# DAC_GainOutputStage8.net
KiCad netlist of a schematic drawn in EAGLE
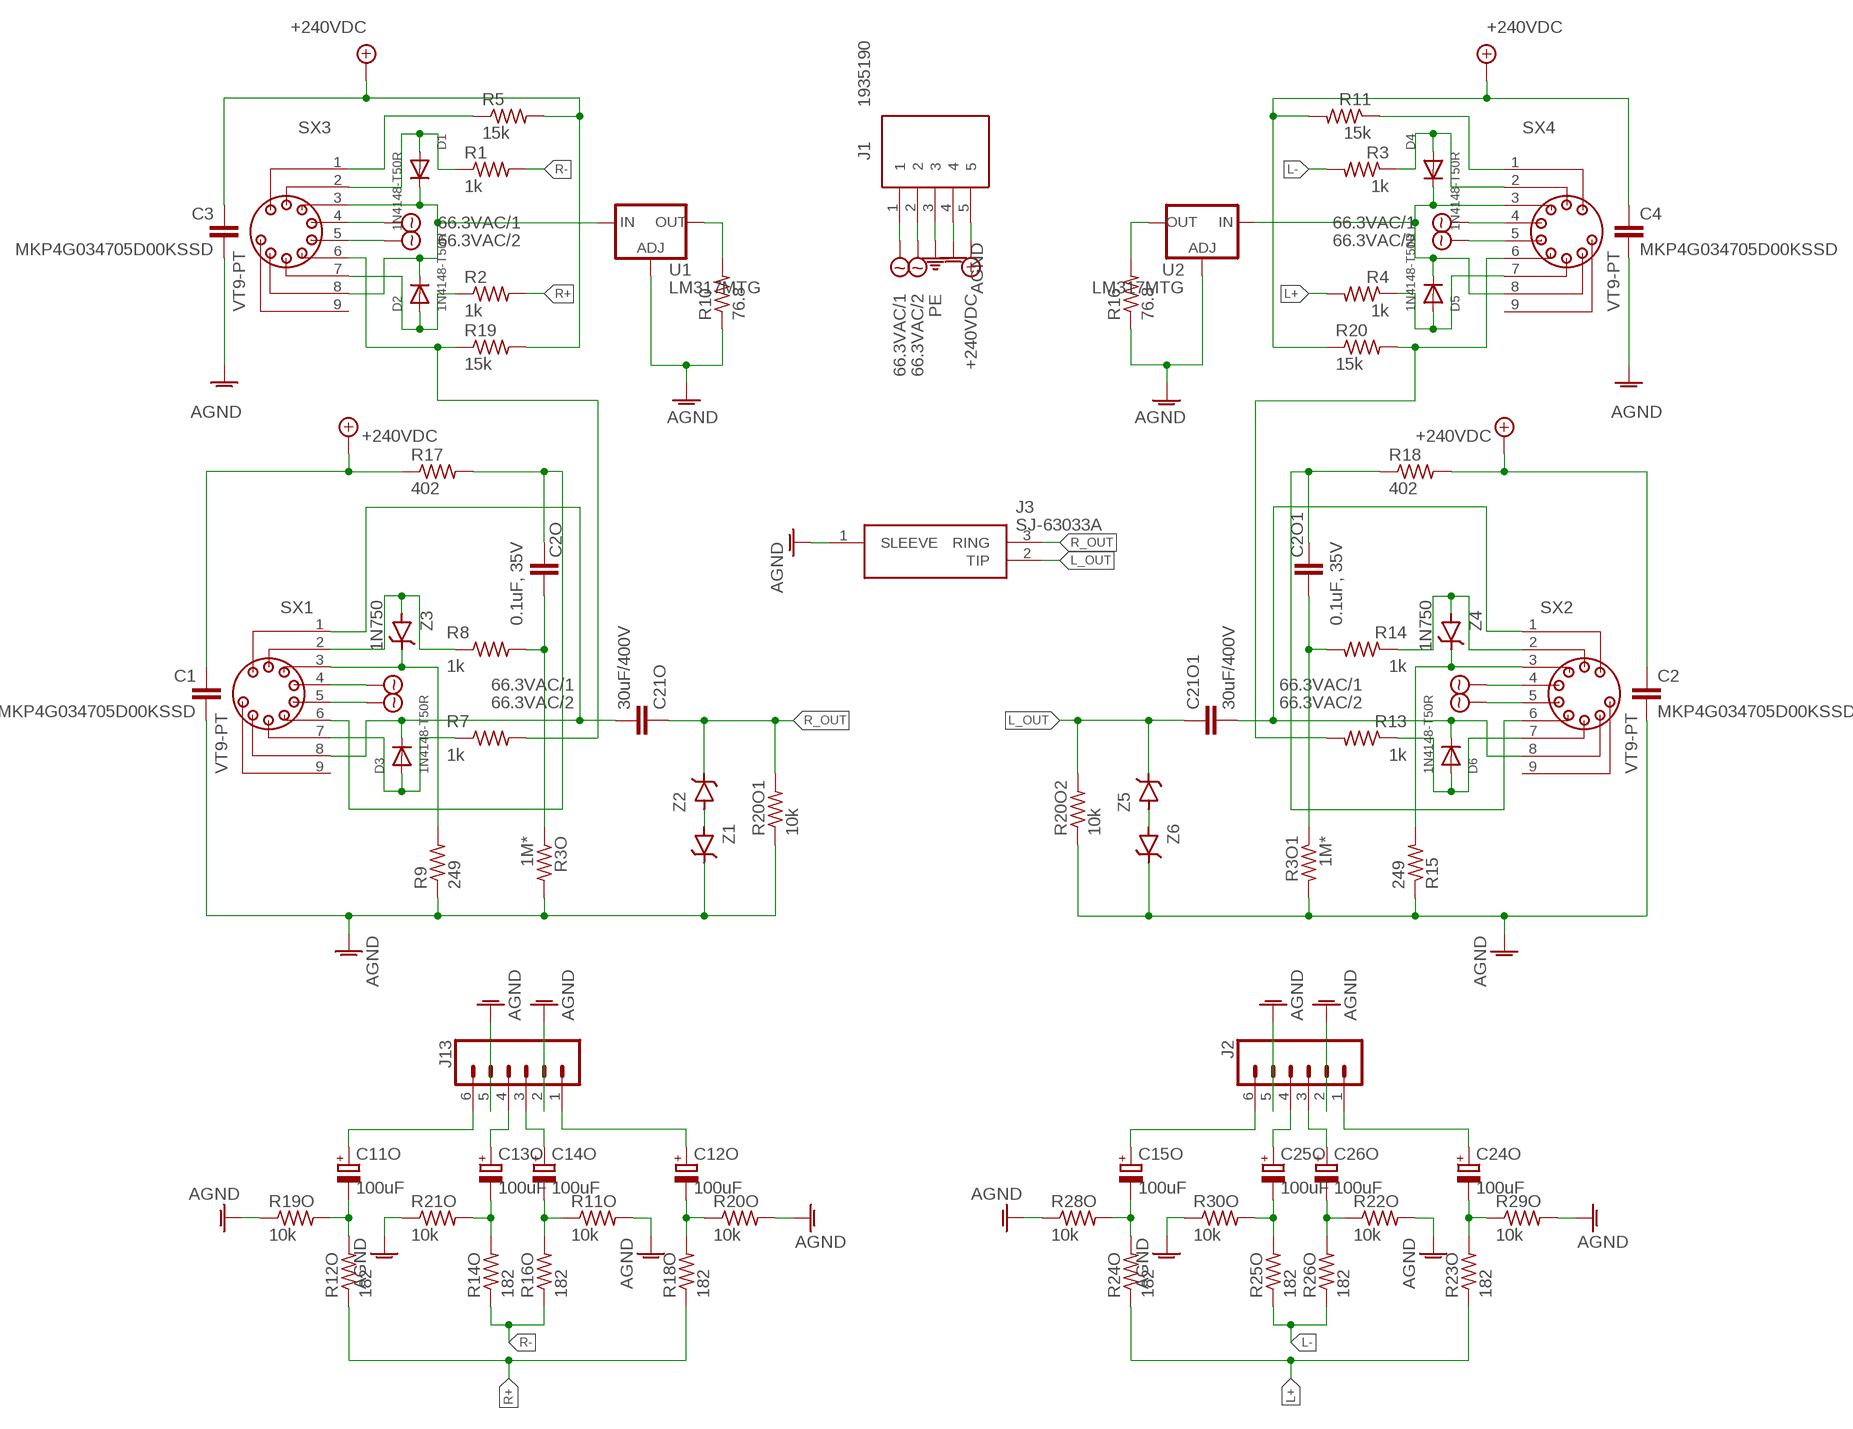
[diagram p0: schematic, sheet 1]

(export (version "E")
  (design (tool "Eeschema 10.0.6"))
  (components
    (comp (ref "C1")
      (value "MKP4G034705D00KSSD")
      (footprint "eagle-import:MKP4G034705D00KSSD")
      (fields (field (name "MOUSER_PART_NUMBER") "505-MKP4G034705DKSSD"))
      (libsource (lib "eagle-import") (part "MKP4G034705D00KSSD"))
    )
    (comp (ref "C2")
      (value "MKP4G034705D00KSSD")
      (footprint "eagle-import:MKP4G034705D00KSSD")
      (fields (field (name "MOUSER_PART_NUMBER") "505-MKP4G034705DKSSD"))
      (libsource (lib "eagle-import") (part "MKP4G034705D00KSSD"))
    )
    (comp (ref "C2O")
      (value "0.1uF, 35V")
      (footprint "eagle-import:MKS4B031002A00JC00")
      (fields
        (field (name "MANUFACTURER_PART_NUMBER") "MKS4B031002A00JC00")
        (field (name "MOUSER_PART_NUMBER") "505-MKS4B0312AJC")
      )
      (libsource (lib "eagle-import") (part "MKS4B031002A00JC00"))
    )
    (comp (ref "C2O1")
      (value "0.1uF, 35V")
      (footprint "eagle-import:MKS4B031002A00JC00")
      (fields
        (field (name "MANUFACTURER_PART_NUMBER") "MKS4B031002A00JC00")
        (field (name "MOUSER_PART_NUMBER") "505-MKS4B0312AJC")
      )
      (libsource (lib "eagle-import") (part "MKS4B031002A00JC00"))
    )
    (comp (ref "C3")
      (value "MKP4G034705D00KSSD")
      (footprint "eagle-import:MKP4G034705D00KSSD")
      (fields (field (name "MOUSER_PART_NUMBER") "505-MKP4G034705DKSSD"))
      (libsource (lib "eagle-import") (part "MKP4G034705D00KSSD"))
    )
    (comp (ref "C4")
      (value "MKP4G034705D00KSSD")
      (footprint "eagle-import:MKP4G034705D00KSSD")
      (fields (field (name "MOUSER_PART_NUMBER") "505-MKP4G034705DKSSD"))
      (libsource (lib "eagle-import") (part "MKP4G034705D00KSSD"))
    )
    (comp (ref "C11O")
      (value "100uF")
      (footprint "eagle-import:CAPPRD350W60D825H1300")
      (fields
        (field (name "ARROW_PART_NUMBER") "UFW1H101MPD1TD")
        (field (name "MOUSER_PART_NUMBER") "647-UFW1H101MPD1TD")
      )
      (libsource (lib "eagle-import") (part "UFW1H101MPD1TD"))
    )
    (comp (ref "C12O")
      (value "100uF")
      (footprint "eagle-import:CAPPRD350W60D825H1300")
      (fields
        (field (name "ARROW_PART_NUMBER") "UFW1H101MPD1TD")
        (field (name "MOUSER_PART_NUMBER") "647-UFW1H101MPD1TD")
      )
      (libsource (lib "eagle-import") (part "UFW1H101MPD1TD"))
    )
    (comp (ref "C13O")
      (value "100uF")
      (footprint "eagle-import:CAPPRD350W60D825H1300")
      (fields
        (field (name "ARROW_PART_NUMBER") "UFW1H101MPD1TD")
        (field (name "MOUSER_PART_NUMBER") "647-UFW1H101MPD1TD")
      )
      (libsource (lib "eagle-import") (part "UFW1H101MPD1TD"))
    )
    (comp (ref "C14O")
      (value "100uF")
      (footprint "eagle-import:CAPPRD350W60D825H1300")
      (fields
        (field (name "ARROW_PART_NUMBER") "UFW1H101MPD1TD")
        (field (name "MOUSER_PART_NUMBER") "647-UFW1H101MPD1TD")
      )
      (libsource (lib "eagle-import") (part "UFW1H101MPD1TD"))
    )
    (comp (ref "C15O")
      (value "100uF")
      (footprint "eagle-import:CAPPRD350W60D825H1300")
      (fields
        (field (name "ARROW_PART_NUMBER") "UFW1H101MPD1TD")
        (field (name "MOUSER_PART_NUMBER") "647-UFW1H101MPD1TD")
      )
      (libsource (lib "eagle-import") (part "UFW1H101MPD1TD"))
    )
    (comp (ref "C21O")
      (value "30uF/400V")
      (footprint "eagle-import:DCP4G056007GD4KSSD")
      (fields
        (field (name "MANUFACTURER_PART_NUMBER") "DCP4G056007GD4KSSD")
        (field (name "MOUSER_PART_NUMBER") "505-DCP4G056007GD4KS")
      )
      (libsource (lib "eagle-import") (part "DCP4G056007GD4KSSD"))
    )
    (comp (ref "C21O1")
      (value "30uF/400V")
      (footprint "eagle-import:DCP4G056007GD4KSSD")
      (fields
        (field (name "MANUFACTURER_PART_NUMBER") "DCP4G056007GD4KSSD")
        (field (name "MOUSER_PART_NUMBER") "505-DCP4G056007GD4KS")
      )
      (libsource (lib "eagle-import") (part "DCP4G056007GD4KSSD"))
    )
    (comp (ref "C24O")
      (value "100uF")
      (footprint "eagle-import:CAPPRD350W60D825H1300")
      (fields
        (field (name "ARROW_PART_NUMBER") "UFW1H101MPD1TD")
        (field (name "MOUSER_PART_NUMBER") "647-UFW1H101MPD1TD")
      )
      (libsource (lib "eagle-import") (part "UFW1H101MPD1TD"))
    )
    (comp (ref "C25O")
      (value "100uF")
      (footprint "eagle-import:CAPPRD350W60D825H1300")
      (fields
        (field (name "ARROW_PART_NUMBER") "UFW1H101MPD1TD")
        (field (name "MOUSER_PART_NUMBER") "647-UFW1H101MPD1TD")
      )
      (libsource (lib "eagle-import") (part "UFW1H101MPD1TD"))
    )
    (comp (ref "C26O")
      (value "100uF")
      (footprint "eagle-import:CAPPRD350W60D825H1300")
      (fields
        (field (name "ARROW_PART_NUMBER") "UFW1H101MPD1TD")
        (field (name "MOUSER_PART_NUMBER") "647-UFW1H101MPD1TD")
      )
      (libsource (lib "eagle-import") (part "UFW1H101MPD1TD"))
    )
    (comp (ref "D1")
      (value "1N4148-T50R")
      (footprint "eagle-import:DIOAD1068W53L380D172")
      (fields (field (name "MOUSER_PART_NUMBER") "512-1N4148T50R"))
      (libsource (lib "eagle-import") (part "1N4148-T50R"))
    )
    (comp (ref "D2")
      (value "1N4148-T50R")
      (footprint "eagle-import:DIOAD1068W53L380D172")
      (fields (field (name "MOUSER_PART_NUMBER") "512-1N4148T50R"))
      (libsource (lib "eagle-import") (part "1N4148-T50R"))
    )
    (comp (ref "D3")
      (value "1N4148-T50R")
      (footprint "eagle-import:DIOAD1068W53L380D172")
      (fields (field (name "MOUSER_PART_NUMBER") "512-1N4148T50R"))
      (libsource (lib "eagle-import") (part "1N4148-T50R"))
    )
    (comp (ref "D4")
      (value "1N4148-T50R")
      (footprint "eagle-import:DIOAD1068W53L380D172")
      (fields (field (name "MOUSER_PART_NUMBER") "512-1N4148T50R"))
      (libsource (lib "eagle-import") (part "1N4148-T50R"))
    )
    (comp (ref "D5")
      (value "1N4148-T50R")
      (footprint "eagle-import:DIOAD1068W53L380D172")
      (fields (field (name "MOUSER_PART_NUMBER") "512-1N4148T50R"))
      (libsource (lib "eagle-import") (part "1N4148-T50R"))
    )
    (comp (ref "D6")
      (value "1N4148-T50R")
      (footprint "eagle-import:DIOAD1068W53L380D172")
      (fields (field (name "MOUSER_PART_NUMBER") "512-1N4148T50R"))
      (libsource (lib "eagle-import") (part "1N4148-T50R"))
    )
    (comp (ref "J1")
      (value "1935190")
      (footprint "eagle-import:1935190")
      (fields (field (name "MOUSER_PART_NUMBER") "651-1935190"))
      (libsource (lib "eagle-import") (part "1935190"))
    )
    (comp (ref "J2")
      (value "CONN_06SILK_FEMALE_PTH")
      (footprint "eagle-import:1X06")
      (libsource (lib "eagle-import") (part "CONN_06SILK_FEMALE_PTH"))
    )
    (comp (ref "J3")
      (value "SJ-63033A")
      (footprint "eagle-import:SJ63033A")
      (libsource (lib "eagle-import") (part "SJ-63033A"))
    )
    (comp (ref "J13")
      (value "CONN_06SILK_FEMALE_PTH")
      (footprint "eagle-import:1X06")
      (libsource (lib "eagle-import") (part "CONN_06SILK_FEMALE_PTH"))
    )
    (comp (ref "R1")
      (value "1k")
      (footprint "eagle-import:0207_10")
      (fields
        (field (name "MANUFACTURER_PART_NUMBER") "LR1F1K0")
        (field (name "MOUSER_PART_NUMBER") "279-LR1F1K0")
      )
      (libsource (lib "eagle-import") (part "LR1F1K0"))
    )
    (comp (ref "R2")
      (value "1k")
      (footprint "eagle-import:0207_10")
      (fields
        (field (name "MANUFACTURER_PART_NUMBER") "LR1F1K0")
        (field (name "MOUSER_PART_NUMBER") "279-LR1F1K0")
      )
      (libsource (lib "eagle-import") (part "LR1F1K0"))
    )
    (comp (ref "R3")
      (value "1k")
      (footprint "eagle-import:0207_10")
      (fields
        (field (name "MANUFACTURER_PART_NUMBER") "LR1F1K0")
        (field (name "MOUSER_PART_NUMBER") "279-LR1F1K0")
      )
      (libsource (lib "eagle-import") (part "LR1F1K0"))
    )
    (comp (ref "R3O")
      (value "1M*")
      (footprint "eagle-import:0207_10")
      (fields
        (field (name "MANUFACTURER_PART_NUMBER") "LR1F1M0")
        (field (name "MOUSER_PART_NUMBER") "279-LR1F1M0")
      )
      (libsource (lib "eagle-import") (part "LR1F1M0"))
    )
    (comp (ref "R3O1")
      (value "1M*")
      (footprint "eagle-import:0207_10")
      (fields
        (field (name "MANUFACTURER_PART_NUMBER") "LR1F1M0")
        (field (name "MOUSER_PART_NUMBER") "279-LR1F1M0")
      )
      (libsource (lib "eagle-import") (part "LR1F1M0"))
    )
    (comp (ref "R4")
      (value "1k")
      (footprint "eagle-import:0207_10")
      (fields
        (field (name "MANUFACTURER_PART_NUMBER") "LR1F1K0")
        (field (name "MOUSER_PART_NUMBER") "279-LR1F1K0")
      )
      (libsource (lib "eagle-import") (part "LR1F1K0"))
    )
    (comp (ref "R5")
      (value "15k")
      (footprint "eagle-import:0411_15")
      (fields
        (field (name "MANUFACTURER_PART_NUMBER") "CPF215K000FKE14")
        (field (name "MOUSER_PART_NUMBER") "71-CPF2-F-15K-E3")
      )
      (libsource (lib "eagle-import") (part "CPF215K000FKE14"))
    )
    (comp (ref "R7")
      (value "1k")
      (footprint "eagle-import:0207_10")
      (fields
        (field (name "MANUFACTURER_PART_NUMBER") "LR1F1K0")
        (field (name "MOUSER_PART_NUMBER") "279-LR1F1K0")
      )
      (libsource (lib "eagle-import") (part "LR1F1K0"))
    )
    (comp (ref "R8")
      (value "1k")
      (footprint "eagle-import:0207_10")
      (fields
        (field (name "MANUFACTURER_PART_NUMBER") "LR1F1K0")
        (field (name "MOUSER_PART_NUMBER") "279-LR1F1K0")
      )
      (libsource (lib "eagle-import") (part "LR1F1K0"))
    )
    (comp (ref "R9")
      (value "249")
      (footprint "eagle-import:0207_10")
      (fields (field (name "MANUFACTURER_PART_NUMBER") "MBB02070C2490FRP00"))
      (libsource (lib "eagle-import") (part "MBB02070C2490FRP00"))
    )
    (comp (ref "R10")
      (value "76.8")
      (footprint "eagle-import:0207_10")
      (fields (field (name "MANUFACTURER_PART_NUMBER") "YR1B76R8CC"))
      (libsource (lib "eagle-import") (part "YR1B76R8CC"))
    )
    (comp (ref "R11")
      (value "15k")
      (footprint "eagle-import:0411_15")
      (fields
        (field (name "MANUFACTURER_PART_NUMBER") "CPF215K000FKE14")
        (field (name "MOUSER_PART_NUMBER") "71-CPF2-F-15K-E3")
      )
      (libsource (lib "eagle-import") (part "CPF215K000FKE14"))
    )
    (comp (ref "R11O")
      (value "10k")
      (footprint "eagle-import:0207_10")
      (fields
        (field (name "MANUFACTURER_PART_NUMBER") "LR1F10K")
        (field (name "MOUSER_PART_NUMBER") "279-LR1F10K")
      )
      (libsource (lib "eagle-import") (part "LR1F10K"))
    )
    (comp (ref "R12O")
      (value "182")
      (footprint "eagle-import:0207_10")
      (fields
        (field (name "MANUFACTURER") "Yageo")
        (field (name "MANUFACTURER_PART_NUMBER") "MF0207FTE52-182R")
        (field (name "MOUSER_PART_NUMBER") "603-MF0207FTE52-182R")
      )
      (libsource (lib "eagle-import") (part "MF0207FTE52-182R"))
    )
    (comp (ref "R13")
      (value "1k")
      (footprint "eagle-import:0207_10")
      (fields
        (field (name "MANUFACTURER_PART_NUMBER") "LR1F1K0")
        (field (name "MOUSER_PART_NUMBER") "279-LR1F1K0")
      )
      (libsource (lib "eagle-import") (part "LR1F1K0"))
    )
    (comp (ref "R14")
      (value "1k")
      (footprint "eagle-import:0207_10")
      (fields
        (field (name "MANUFACTURER_PART_NUMBER") "LR1F1K0")
        (field (name "MOUSER_PART_NUMBER") "279-LR1F1K0")
      )
      (libsource (lib "eagle-import") (part "LR1F1K0"))
    )
    (comp (ref "R14O")
      (value "182")
      (footprint "eagle-import:0207_10")
      (fields
        (field (name "MANUFACTURER") "Yageo")
        (field (name "MANUFACTURER_PART_NUMBER") "MF0207FTE52-182R")
        (field (name "MOUSER_PART_NUMBER") "603-MF0207FTE52-182R")
      )
      (libsource (lib "eagle-import") (part "MF0207FTE52-182R"))
    )
    (comp (ref "R15")
      (value "249")
      (footprint "eagle-import:0207_10")
      (fields (field (name "MANUFACTURER_PART_NUMBER") "MBB02070C2490FRP00"))
      (libsource (lib "eagle-import") (part "MBB02070C2490FRP00"))
    )
    (comp (ref "R16")
      (value "76.8")
      (footprint "eagle-import:0207_10")
      (fields (field (name "MANUFACTURER_PART_NUMBER") "YR1B76R8CC"))
      (libsource (lib "eagle-import") (part "YR1B76R8CC"))
    )
    (comp (ref "R16O")
      (value "182")
      (footprint "eagle-import:0207_10")
      (fields
        (field (name "MANUFACTURER") "Yageo")
        (field (name "MANUFACTURER_PART_NUMBER") "MF0207FTE52-182R")
        (field (name "MOUSER_PART_NUMBER") "603-MF0207FTE52-182R")
      )
      (libsource (lib "eagle-import") (part "MF0207FTE52-182R"))
    )
    (comp (ref "R17")
      (value "402")
      (footprint "eagle-import:0617_22")
      (fields (field (name "MANUFACTURER_PART_NUMBER") "RWR80S4020FRB12"))
      (libsource (lib "eagle-import") (part "RWR80S4020FRB12"))
    )
    (comp (ref "R18")
      (value "402")
      (footprint "eagle-import:0617_22")
      (fields (field (name "MANUFACTURER_PART_NUMBER") "RWR80S4020FRB12"))
      (libsource (lib "eagle-import") (part "RWR80S4020FRB12"))
    )
    (comp (ref "R18O")
      (value "182")
      (footprint "eagle-import:0207_10")
      (fields
        (field (name "MANUFACTURER") "Yageo")
        (field (name "MANUFACTURER_PART_NUMBER") "MF0207FTE52-182R")
        (field (name "MOUSER_PART_NUMBER") "603-MF0207FTE52-182R")
      )
      (libsource (lib "eagle-import") (part "MF0207FTE52-182R"))
    )
    (comp (ref "R19")
      (value "15k")
      (footprint "eagle-import:0411_15")
      (fields
        (field (name "MANUFACTURER_PART_NUMBER") "CPF215K000FKE14")
        (field (name "MOUSER_PART_NUMBER") "71-CPF2-F-15K-E3")
      )
      (libsource (lib "eagle-import") (part "CPF215K000FKE14"))
    )
    (comp (ref "R19O")
      (value "10k")
      (footprint "eagle-import:0207_10")
      (fields
        (field (name "MANUFACTURER_PART_NUMBER") "LR1F10K")
        (field (name "MOUSER_PART_NUMBER") "279-LR1F10K")
      )
      (libsource (lib "eagle-import") (part "LR1F10K"))
    )
    (comp (ref "R20")
      (value "15k")
      (footprint "eagle-import:0411_15")
      (fields
        (field (name "MANUFACTURER_PART_NUMBER") "CPF215K000FKE14")
        (field (name "MOUSER_PART_NUMBER") "71-CPF2-F-15K-E3")
      )
      (libsource (lib "eagle-import") (part "CPF215K000FKE14"))
    )
    (comp (ref "R20O")
      (value "10k")
      (footprint "eagle-import:0207_10")
      (fields
        (field (name "MANUFACTURER_PART_NUMBER") "LR1F10K")
        (field (name "MOUSER_PART_NUMBER") "279-LR1F10K")
      )
      (libsource (lib "eagle-import") (part "LR1F10K"))
    )
    (comp (ref "R20O1")
      (value "10k")
      (footprint "eagle-import:0207_10")
      (fields
        (field (name "MANUFACTURER_PART_NUMBER") "LR1F10K")
        (field (name "MOUSER_PART_NUMBER") "279-LR1F10K")
      )
      (libsource (lib "eagle-import") (part "LR1F10K"))
    )
    (comp (ref "R20O2")
      (value "10k")
      (footprint "eagle-import:0207_10")
      (fields
        (field (name "MANUFACTURER_PART_NUMBER") "LR1F10K")
        (field (name "MOUSER_PART_NUMBER") "279-LR1F10K")
      )
      (libsource (lib "eagle-import") (part "LR1F10K"))
    )
    (comp (ref "R21O")
      (value "10k")
      (footprint "eagle-import:0207_10")
      (fields
        (field (name "MANUFACTURER_PART_NUMBER") "LR1F10K")
        (field (name "MOUSER_PART_NUMBER") "279-LR1F10K")
      )
      (libsource (lib "eagle-import") (part "LR1F10K"))
    )
    (comp (ref "R22O")
      (value "10k")
      (footprint "eagle-import:0207_10")
      (fields
        (field (name "MANUFACTURER_PART_NUMBER") "LR1F10K")
        (field (name "MOUSER_PART_NUMBER") "279-LR1F10K")
      )
      (libsource (lib "eagle-import") (part "LR1F10K"))
    )
    (comp (ref "R23O")
      (value "182")
      (footprint "eagle-import:0207_10")
      (fields
        (field (name "MANUFACTURER") "Yageo")
        (field (name "MANUFACTURER_PART_NUMBER") "MF0207FTE52-182R")
        (field (name "MOUSER_PART_NUMBER") "603-MF0207FTE52-182R")
      )
      (libsource (lib "eagle-import") (part "MF0207FTE52-182R"))
    )
    (comp (ref "R24O")
      (value "182")
      (footprint "eagle-import:0207_10")
      (fields
        (field (name "MANUFACTURER") "Yageo")
        (field (name "MANUFACTURER_PART_NUMBER") "MF0207FTE52-182R")
        (field (name "MOUSER_PART_NUMBER") "603-MF0207FTE52-182R")
      )
      (libsource (lib "eagle-import") (part "MF0207FTE52-182R"))
    )
    (comp (ref "R25O")
      (value "182")
      (footprint "eagle-import:0207_10")
      (fields
        (field (name "MANUFACTURER") "Yageo")
        (field (name "MANUFACTURER_PART_NUMBER") "MF0207FTE52-182R")
        (field (name "MOUSER_PART_NUMBER") "603-MF0207FTE52-182R")
      )
      (libsource (lib "eagle-import") (part "MF0207FTE52-182R"))
    )
    (comp (ref "R26O")
      (value "182")
      (footprint "eagle-import:0207_10")
      (fields
        (field (name "MANUFACTURER") "Yageo")
        (field (name "MANUFACTURER_PART_NUMBER") "MF0207FTE52-182R")
        (field (name "MOUSER_PART_NUMBER") "603-MF0207FTE52-182R")
      )
      (libsource (lib "eagle-import") (part "MF0207FTE52-182R"))
    )
    (comp (ref "R28O")
      (value "10k")
      (footprint "eagle-import:0207_10")
      (fields
        (field (name "MANUFACTURER_PART_NUMBER") "LR1F10K")
        (field (name "MOUSER_PART_NUMBER") "279-LR1F10K")
      )
      (libsource (lib "eagle-import") (part "LR1F10K"))
    )
    (comp (ref "R29O")
      (value "10k")
      (footprint "eagle-import:0207_10")
      (fields
        (field (name "MANUFACTURER_PART_NUMBER") "LR1F10K")
        (field (name "MOUSER_PART_NUMBER") "279-LR1F10K")
      )
      (libsource (lib "eagle-import") (part "LR1F10K"))
    )
    (comp (ref "R30O")
      (value "10k")
      (footprint "eagle-import:0207_10")
      (fields
        (field (name "MANUFACTURER_PART_NUMBER") "LR1F10K")
        (field (name "MOUSER_PART_NUMBER") "279-LR1F10K")
      )
      (libsource (lib "eagle-import") (part "LR1F10K"))
    )
    (comp (ref "SX1")
      (value "VT9-PT")
      (footprint "eagle-import:VT9-PT")
      (libsource (lib "eagle-import") (part "VT9-PT"))
    )
    (comp (ref "SX2")
      (value "VT9-PT")
      (footprint "eagle-import:VT9-PT")
      (libsource (lib "eagle-import") (part "VT9-PT"))
    )
    (comp (ref "SX3")
      (value "VT9-PT")
      (footprint "eagle-import:VT9-PT")
      (libsource (lib "eagle-import") (part "VT9-PT"))
    )
    (comp (ref "SX4")
      (value "VT9-PT")
      (footprint "eagle-import:VT9-PT")
      (libsource (lib "eagle-import") (part "VT9-PT"))
    )
    (comp (ref "U1")
      (value "LM317MTG")
      (footprint "eagle-import:TO254P482X997X2018-3P")
      (fields (field (name "MOUSER_PART_NUMBER") "863-LM317MTG"))
      (libsource (lib "eagle-import") (part "LM317MTG"))
    )
    (comp (ref "U2")
      (value "LM317MTG")
      (footprint "eagle-import:TO254P482X997X2018-3P")
      (fields (field (name "MOUSER_PART_NUMBER") "863-LM317MTG"))
      (libsource (lib "eagle-import") (part "LM317MTG"))
    )
    (comp (ref "Z1")
      (value "BZX79-C16,113")
      (footprint "eagle-import:DIOAD1165W56L425D185")
      (libsource (lib "eagle-import") (part "BZX79-C16,113"))
    )
    (comp (ref "Z2")
      (value "BZX79-C16,113")
      (footprint "eagle-import:DIOAD1165W56L425D185")
      (libsource (lib "eagle-import") (part "BZX79-C16,113"))
    )
    (comp (ref "Z3")
      (value "1N750")
      (footprint "eagle-import:DIOAD1256W56L444D203")
      (fields (field (name "MOUSER_PART_NUMBER") "494-1N750(DO-35)"))
      (libsource (lib "eagle-import") (part "1N750"))
    )
    (comp (ref "Z4")
      (value "1N750")
      (footprint "eagle-import:DIOAD1256W56L444D203")
      (fields (field (name "MOUSER_PART_NUMBER") "494-1N750(DO-35)"))
      (libsource (lib "eagle-import") (part "1N750"))
    )
    (comp (ref "Z5")
      (value "BZX79-C16,113")
      (footprint "eagle-import:DIOAD1165W56L425D185")
      (libsource (lib "eagle-import") (part "BZX79-C16,113"))
    )
    (comp (ref "Z6")
      (value "BZX79-C16,113")
      (footprint "eagle-import:DIOAD1165W56L425D185")
      (libsource (lib "eagle-import") (part "BZX79-C16,113"))
    )
  )
  (nets
    (net (code "1") (name "+240VDC") (class "Default")
      (node (ref "C1") (pin "1") (pinfunction "1_1") (pintype "passive"))
      (node (ref "C2") (pin "1") (pinfunction "1_1") (pintype "passive"))
      (node (ref "C3") (pin "1") (pinfunction "1_1") (pintype "passive"))
      (node (ref "C4") (pin "1") (pinfunction "1_1") (pintype "passive"))
      (node (ref "J1") (pin "5") (pinfunction "5_5") (pintype "bidirectional"))
      (node (ref "R11") (pin "2") (pinfunction "2_2") (pintype "passive"))
      (node (ref "R17") (pin "1") (pinfunction "1_1") (pintype "passive"))
      (node (ref "R18") (pin "2") (pinfunction "2_2") (pintype "passive"))
      (node (ref "R19") (pin "2") (pinfunction "2_2") (pintype "passive"))
      (node (ref "R20") (pin "1") (pinfunction "1_1") (pintype "passive"))
      (node (ref "R5") (pin "2") (pinfunction "2_2") (pintype "passive"))
    )
    (net (code "2") (name "66.3VAC{slash}1") (class "Default")
      (node (ref "J1") (pin "1") (pinfunction "1_1") (pintype "bidirectional"))
      (node (ref "SX1") (pin "4") (pinfunction "4_4") (pintype "passive"))
      (node (ref "SX2") (pin "4") (pinfunction "4_4") (pintype "passive"))
      (node (ref "SX3") (pin "4") (pinfunction "4_4") (pintype "passive"))
      (node (ref "SX4") (pin "4") (pinfunction "4_4") (pintype "passive"))
    )
    (net (code "3") (name "66.3VAC{slash}2") (class "Default")
      (node (ref "J1") (pin "2") (pinfunction "2_2") (pintype "bidirectional"))
      (node (ref "SX1") (pin "5") (pinfunction "5_5") (pintype "passive"))
      (node (ref "SX2") (pin "5") (pinfunction "5_5") (pintype "passive"))
      (node (ref "SX3") (pin "5") (pinfunction "5_5") (pintype "passive"))
      (node (ref "SX4") (pin "5") (pinfunction "5_5") (pintype "passive"))
    )
    (net (code "4") (name "AGND") (class "Default")
      (node (ref "C1") (pin "2") (pinfunction "2_2") (pintype "passive"))
      (node (ref "C2") (pin "2") (pinfunction "2_2") (pintype "passive"))
      (node (ref "C3") (pin "2") (pinfunction "2_2") (pintype "passive"))
      (node (ref "C4") (pin "2") (pinfunction "2_2") (pintype "passive"))
      (node (ref "J1") (pin "4") (pinfunction "4_4") (pintype "bidirectional"))
      (node (ref "J13") (pin "2") (pinfunction "2_2") (pintype "passive"))
      (node (ref "J13") (pin "5") (pinfunction "5_5") (pintype "passive"))
      (node (ref "J2") (pin "2") (pinfunction "2_2") (pintype "passive"))
      (node (ref "J2") (pin "5") (pinfunction "5_5") (pintype "passive"))
      (node (ref "J3") (pin "1") (pinfunction "SLEEVE_1") (pintype "bidirectional"))
      (node (ref "R10") (pin "1") (pinfunction "1_1") (pintype "passive"))
      (node (ref "R11O") (pin "2") (pinfunction "2_2") (pintype "passive"))
      (node (ref "R15") (pin "1") (pinfunction "1_1") (pintype "passive"))
      (node (ref "R16") (pin "1") (pinfunction "1_1") (pintype "passive"))
      (node (ref "R19O") (pin "1") (pinfunction "1_1") (pintype "passive"))
      (node (ref "R20O") (pin "2") (pinfunction "2_2") (pintype "passive"))
      (node (ref "R20O1") (pin "1") (pinfunction "1_1") (pintype "passive"))
      (node (ref "R20O2") (pin "1") (pinfunction "1_1") (pintype "passive"))
      (node (ref "R21O") (pin "1") (pinfunction "1_1") (pintype "passive"))
      (node (ref "R22O") (pin "2") (pinfunction "2_2") (pintype "passive"))
      (node (ref "R28O") (pin "1") (pinfunction "1_1") (pintype "passive"))
      (node (ref "R29O") (pin "2") (pinfunction "2_2") (pintype "passive"))
      (node (ref "R30O") (pin "1") (pinfunction "1_1") (pintype "passive"))
      (node (ref "R3O") (pin "2") (pinfunction "2_2") (pintype "passive"))
      (node (ref "R3O1") (pin "2") (pinfunction "2_2") (pintype "passive"))
      (node (ref "R9") (pin "1") (pinfunction "1_1") (pintype "passive"))
      (node (ref "U1") (pin "1") (pinfunction "ADJ_1") (pintype "input"))
      (node (ref "U2") (pin "1") (pinfunction "ADJ_1") (pintype "input"))
      (node (ref "Z1") (pin "1") (pinfunction "C_1") (pintype "passive"))
      (node (ref "Z6") (pin "1") (pinfunction "C_1") (pintype "passive"))
    )
    (net (code "5") (name "L+") (class "Default")
      (node (ref "R23O") (pin "1") (pinfunction "1_1") (pintype "passive"))
      (node (ref "R24O") (pin "1") (pinfunction "1_1") (pintype "passive"))
      (node (ref "R4") (pin "2") (pinfunction "2_2") (pintype "passive"))
    )
    (net (code "6") (name "L-") (class "Default")
      (node (ref "R25O") (pin "1") (pinfunction "1_1") (pintype "passive"))
      (node (ref "R26O") (pin "1") (pinfunction "1_1") (pintype "passive"))
      (node (ref "R3") (pin "2") (pinfunction "2_2") (pintype "passive"))
    )
    (net (code "7") (name "L_OUT") (class "Default")
      (node (ref "C21O1") (pin "1") (pinfunction "1_1") (pintype "passive"))
      (node (ref "C21O1") (pin "4") (pinfunction "1_4") (pintype "passive"))
      (node (ref "J3") (pin "2") (pinfunction "TIP_2") (pintype "bidirectional"))
      (node (ref "R20O2") (pin "2") (pinfunction "2_2") (pintype "passive"))
      (node (ref "Z5") (pin "1") (pinfunction "C_1") (pintype "passive"))
    )
    (net (code "8") (name "Net-(C2O-Pad1)") (class "Default")
      (node (ref "C2O") (pin "1") (pinfunction "1_1") (pintype "passive"))
      (node (ref "R17") (pin "2") (pinfunction "2_2") (pintype "passive"))
      (node (ref "SX1") (pin "6") (pinfunction "6_6") (pintype "passive"))
    )
    (net (code "9") (name "Net-(C2O-Pad2)") (class "Default")
      (node (ref "C2O") (pin "2") (pinfunction "2_2") (pintype "passive"))
      (node (ref "R3O") (pin "1") (pinfunction "1_1") (pintype "passive"))
      (node (ref "R8") (pin "2") (pinfunction "2_2") (pintype "passive"))
    )
    (net (code "10") (name "Net-(C2O1-Pad1)") (class "Default")
      (node (ref "C2O1") (pin "1") (pinfunction "1_1") (pintype "passive"))
      (node (ref "R18") (pin "1") (pinfunction "1_1") (pintype "passive"))
      (node (ref "SX2") (pin "6") (pinfunction "6_6") (pintype "passive"))
    )
    (net (code "11") (name "Net-(C2O1-Pad2)") (class "Default")
      (node (ref "C2O1") (pin "2") (pinfunction "2_2") (pintype "passive"))
      (node (ref "R14") (pin "2") (pinfunction "2_2") (pintype "passive"))
      (node (ref "R3O1") (pin "1") (pinfunction "1_1") (pintype "passive"))
    )
    (net (code "12") (name "Net-(C11O-+)") (class "Default")
      (node (ref "C11O") (pin "1") (pinfunction "+_1") (pintype "passive"))
      (node (ref "J13") (pin "6") (pinfunction "6_6") (pintype "passive"))
    )
    (net (code "13") (name "Net-(C11O--)") (class "Default")
      (node (ref "C11O") (pin "2") (pinfunction "-_2") (pintype "passive"))
      (node (ref "R12O") (pin "2") (pinfunction "2_2") (pintype "passive"))
      (node (ref "R19O") (pin "2") (pinfunction "2_2") (pintype "passive"))
    )
    (net (code "14") (name "Net-(C12O-+)") (class "Default")
      (node (ref "C12O") (pin "1") (pinfunction "+_1") (pintype "passive"))
      (node (ref "J13") (pin "1") (pinfunction "1_1") (pintype "passive"))
    )
    (net (code "15") (name "Net-(C12O--)") (class "Default")
      (node (ref "C12O") (pin "2") (pinfunction "-_2") (pintype "passive"))
      (node (ref "R18O") (pin "2") (pinfunction "2_2") (pintype "passive"))
      (node (ref "R20O") (pin "1") (pinfunction "1_1") (pintype "passive"))
    )
    (net (code "16") (name "Net-(C13O-+)") (class "Default")
      (node (ref "C13O") (pin "1") (pinfunction "+_1") (pintype "passive"))
      (node (ref "J13") (pin "4") (pinfunction "4_4") (pintype "passive"))
    )
    (net (code "17") (name "Net-(C13O--)") (class "Default")
      (node (ref "C13O") (pin "2") (pinfunction "-_2") (pintype "passive"))
      (node (ref "R14O") (pin "2") (pinfunction "2_2") (pintype "passive"))
      (node (ref "R21O") (pin "2") (pinfunction "2_2") (pintype "passive"))
    )
    (net (code "18") (name "Net-(C14O-+)") (class "Default")
      (node (ref "C14O") (pin "1") (pinfunction "+_1") (pintype "passive"))
      (node (ref "J13") (pin "3") (pinfunction "3_3") (pintype "passive"))
    )
    (net (code "19") (name "Net-(C14O--)") (class "Default")
      (node (ref "C14O") (pin "2") (pinfunction "-_2") (pintype "passive"))
      (node (ref "R11O") (pin "1") (pinfunction "1_1") (pintype "passive"))
      (node (ref "R16O") (pin "2") (pinfunction "2_2") (pintype "passive"))
    )
    (net (code "20") (name "Net-(C15O-+)") (class "Default")
      (node (ref "C15O") (pin "1") (pinfunction "+_1") (pintype "passive"))
      (node (ref "J2") (pin "6") (pinfunction "6_6") (pintype "passive"))
    )
    (net (code "21") (name "Net-(C15O--)") (class "Default")
      (node (ref "C15O") (pin "2") (pinfunction "-_2") (pintype "passive"))
      (node (ref "R24O") (pin "2") (pinfunction "2_2") (pintype "passive"))
      (node (ref "R28O") (pin "2") (pinfunction "2_2") (pintype "passive"))
    )
    (net (code "22") (name "Net-(C24O-+)") (class "Default")
      (node (ref "C24O") (pin "1") (pinfunction "+_1") (pintype "passive"))
      (node (ref "J2") (pin "1") (pinfunction "1_1") (pintype "passive"))
    )
    (net (code "23") (name "Net-(C24O--)") (class "Default")
      (node (ref "C24O") (pin "2") (pinfunction "-_2") (pintype "passive"))
      (node (ref "R23O") (pin "2") (pinfunction "2_2") (pintype "passive"))
      (node (ref "R29O") (pin "1") (pinfunction "1_1") (pintype "passive"))
    )
    (net (code "24") (name "Net-(C25O-+)") (class "Default")
      (node (ref "C25O") (pin "1") (pinfunction "+_1") (pintype "passive"))
      (node (ref "J2") (pin "4") (pinfunction "4_4") (pintype "passive"))
    )
    (net (code "25") (name "Net-(C25O--)") (class "Default")
      (node (ref "C25O") (pin "2") (pinfunction "-_2") (pintype "passive"))
      (node (ref "R25O") (pin "2") (pinfunction "2_2") (pintype "passive"))
      (node (ref "R30O") (pin "2") (pinfunction "2_2") (pintype "passive"))
    )
    (net (code "26") (name "Net-(C26O-+)") (class "Default")
      (node (ref "C26O") (pin "1") (pinfunction "+_1") (pintype "passive"))
      (node (ref "J2") (pin "3") (pinfunction "3_3") (pintype "passive"))
    )
    (net (code "27") (name "Net-(C26O--)") (class "Default")
      (node (ref "C26O") (pin "2") (pinfunction "-_2") (pintype "passive"))
      (node (ref "R22O") (pin "1") (pinfunction "1_1") (pintype "passive"))
      (node (ref "R26O") (pin "2") (pinfunction "2_2") (pintype "passive"))
    )
    (net (code "28") (name "Net-(D1-A)") (class "Default")
      (node (ref "D1") (pin "2") (pinfunction "A_2") (pintype "passive"))
      (node (ref "R1") (pin "1") (pinfunction "1_1") (pintype "passive"))
      (node (ref "SX3") (pin "2") (pinfunction "2_2") (pintype "passive"))
    )
    (net (code "29") (name "Net-(D1-C)") (class "Default")
      (node (ref "D1") (pin "1") (pinfunction "C_1") (pintype "passive"))
      (node (ref "D2") (pin "1") (pinfunction "C_1") (pintype "passive"))
      (node (ref "SX3") (pin "3") (pinfunction "3_3") (pintype "passive"))
      (node (ref "SX3") (pin "8") (pinfunction "8_8") (pintype "passive"))
      (node (ref "U1") (pin "3") (pinfunction "IN_3") (pintype "input"))
    )
    (net (code "30") (name "Net-(D2-A)") (class "Default")
      (node (ref "D2") (pin "2") (pinfunction "A_2") (pintype "passive"))
      (node (ref "R2") (pin "1") (pinfunction "1_1") (pintype "passive"))
      (node (ref "SX3") (pin "7") (pinfunction "7_7") (pintype "passive"))
    )
    (net (code "31") (name "Net-(D3-A)") (class "Default")
      (node (ref "D3") (pin "2") (pinfunction "A_2") (pintype "passive"))
      (node (ref "R7") (pin "1") (pinfunction "1_1") (pintype "passive"))
      (node (ref "SX1") (pin "7") (pinfunction "7_7") (pintype "passive"))
    )
    (net (code "32") (name "Net-(D3-C)") (class "Default")
      (node (ref "C21O") (pin "2") (pinfunction "2_2") (pintype "passive"))
      (node (ref "C21O") (pin "3") (pinfunction "2_3") (pintype "passive"))
      (node (ref "D3") (pin "1") (pinfunction "C_1") (pintype "passive"))
      (node (ref "SX1") (pin "1") (pinfunction "1_1") (pintype "passive"))
      (node (ref "SX1") (pin "8") (pinfunction "8_8") (pintype "passive"))
    )
    (net (code "33") (name "Net-(D4-A)") (class "Default")
      (node (ref "D4") (pin "2") (pinfunction "A_2") (pintype "passive"))
      (node (ref "R3") (pin "1") (pinfunction "1_1") (pintype "passive"))
      (node (ref "SX4") (pin "2") (pinfunction "2_2") (pintype "passive"))
    )
    (net (code "34") (name "Net-(D4-C)") (class "Default")
      (node (ref "D4") (pin "1") (pinfunction "C_1") (pintype "passive"))
      (node (ref "D5") (pin "1") (pinfunction "C_1") (pintype "passive"))
      (node (ref "SX4") (pin "3") (pinfunction "3_3") (pintype "passive"))
      (node (ref "SX4") (pin "8") (pinfunction "8_8") (pintype "passive"))
      (node (ref "U2") (pin "3") (pinfunction "IN_3") (pintype "input"))
    )
    (net (code "35") (name "Net-(D5-A)") (class "Default")
      (node (ref "D5") (pin "2") (pinfunction "A_2") (pintype "passive"))
      (node (ref "R4") (pin "1") (pinfunction "1_1") (pintype "passive"))
      (node (ref "SX4") (pin "7") (pinfunction "7_7") (pintype "passive"))
    )
    (net (code "36") (name "Net-(D6-A)") (class "Default")
      (node (ref "D6") (pin "2") (pinfunction "A_2") (pintype "passive"))
      (node (ref "R13") (pin "1") (pinfunction "1_1") (pintype "passive"))
      (node (ref "SX2") (pin "7") (pinfunction "7_7") (pintype "passive"))
    )
    (net (code "37") (name "Net-(D6-C)") (class "Default")
      (node (ref "C21O1") (pin "2") (pinfunction "2_2") (pintype "passive"))
      (node (ref "C21O1") (pin "3") (pinfunction "2_3") (pintype "passive"))
      (node (ref "D6") (pin "1") (pinfunction "C_1") (pintype "passive"))
      (node (ref "SX2") (pin "1") (pinfunction "1_1") (pintype "passive"))
      (node (ref "SX2") (pin "8") (pinfunction "8_8") (pintype "passive"))
    )
    (net (code "38") (name "Net-(R5-Pad1)") (class "Default")
      (node (ref "R5") (pin "1") (pinfunction "1_1") (pintype "passive"))
      (node (ref "SX3") (pin "1") (pinfunction "1_1") (pintype "passive"))
    )
    (net (code "39") (name "Net-(R11-Pad1)") (class "Default")
      (node (ref "R11") (pin "1") (pinfunction "1_1") (pintype "passive"))
      (node (ref "SX4") (pin "1") (pinfunction "1_1") (pintype "passive"))
    )
    (net (code "40") (name "Net-(R13-Pad2)") (class "Default")
      (node (ref "R13") (pin "2") (pinfunction "2_2") (pintype "passive"))
      (node (ref "R20") (pin "2") (pinfunction "2_2") (pintype "passive"))
      (node (ref "SX4") (pin "6") (pinfunction "6_6") (pintype "passive"))
    )
    (net (code "41") (name "Net-(R19-Pad1)") (class "Default")
      (node (ref "R19") (pin "1") (pinfunction "1_1") (pintype "passive"))
      (node (ref "R7") (pin "2") (pinfunction "2_2") (pintype "passive"))
      (node (ref "SX3") (pin "6") (pinfunction "6_6") (pintype "passive"))
    )
    (net (code "42") (name "Net-(U1-OUT)") (class "Default")
      (node (ref "R10") (pin "2") (pinfunction "2_2") (pintype "passive"))
      (node (ref "U1") (pin "2") (pinfunction "OUT_2") (pintype "passive"))
    )
    (net (code "43") (name "Net-(U2-OUT)") (class "Default")
      (node (ref "R16") (pin "2") (pinfunction "2_2") (pintype "passive"))
      (node (ref "U2") (pin "2") (pinfunction "OUT_2") (pintype "passive"))
    )
    (net (code "44") (name "Net-(Z1-A)") (class "Default")
      (node (ref "Z1") (pin "2") (pinfunction "A_2") (pintype "passive"))
      (node (ref "Z2") (pin "2") (pinfunction "A_2") (pintype "passive"))
    )
    (net (code "45") (name "Net-(Z3-A)") (class "Default")
      (node (ref "R8") (pin "1") (pinfunction "1_1") (pintype "passive"))
      (node (ref "SX1") (pin "2") (pinfunction "2_2") (pintype "passive"))
      (node (ref "Z3") (pin "2") (pinfunction "A_2") (pintype "passive"))
    )
    (net (code "46") (name "Net-(Z3-C)") (class "Default")
      (node (ref "R9") (pin "2") (pinfunction "2_2") (pintype "passive"))
      (node (ref "SX1") (pin "3") (pinfunction "3_3") (pintype "passive"))
      (node (ref "Z3") (pin "1") (pinfunction "C_1") (pintype "passive"))
    )
    (net (code "47") (name "Net-(Z4-A)") (class "Default")
      (node (ref "R14") (pin "1") (pinfunction "1_1") (pintype "passive"))
      (node (ref "SX2") (pin "2") (pinfunction "2_2") (pintype "passive"))
      (node (ref "Z4") (pin "2") (pinfunction "A_2") (pintype "passive"))
    )
    (net (code "48") (name "Net-(Z4-C)") (class "Default")
      (node (ref "R15") (pin "2") (pinfunction "2_2") (pintype "passive"))
      (node (ref "SX2") (pin "3") (pinfunction "3_3") (pintype "passive"))
      (node (ref "Z4") (pin "1") (pinfunction "C_1") (pintype "passive"))
    )
    (net (code "49") (name "Net-(Z5-A)") (class "Default")
      (node (ref "Z5") (pin "2") (pinfunction "A_2") (pintype "passive"))
      (node (ref "Z6") (pin "2") (pinfunction "A_2") (pintype "passive"))
    )
    (net (code "50") (name "PE") (class "Default")
      (node (ref "J1") (pin "3") (pinfunction "3_3") (pintype "bidirectional"))
    )
    (net (code "51") (name "R+") (class "Default")
      (node (ref "R12O") (pin "1") (pinfunction "1_1") (pintype "passive"))
      (node (ref "R18O") (pin "1") (pinfunction "1_1") (pintype "passive"))
      (node (ref "R2") (pin "2") (pinfunction "2_2") (pintype "passive"))
    )
    (net (code "52") (name "R-") (class "Default")
      (node (ref "R1") (pin "2") (pinfunction "2_2") (pintype "passive"))
      (node (ref "R14O") (pin "1") (pinfunction "1_1") (pintype "passive"))
      (node (ref "R16O") (pin "1") (pinfunction "1_1") (pintype "passive"))
    )
    (net (code "53") (name "R_OUT") (class "Default")
      (node (ref "C21O") (pin "1") (pinfunction "1_1") (pintype "passive"))
      (node (ref "C21O") (pin "4") (pinfunction "1_4") (pintype "passive"))
      (node (ref "J3") (pin "3") (pinfunction "RING_3") (pintype "bidirectional"))
      (node (ref "R20O1") (pin "2") (pinfunction "2_2") (pintype "passive"))
      (node (ref "Z2") (pin "1") (pinfunction "C_1") (pintype "passive"))
    )
    (net (code "54") (name "unconnected-(SX1-Pad9)") (class "Default")
      (node (ref "SX1") (pin "9") (pinfunction "9_9") (pintype "passive"))
    )
    (net (code "55") (name "unconnected-(SX2-Pad9)") (class "Default")
      (node (ref "SX2") (pin "9") (pinfunction "9_9") (pintype "passive"))
    )
    (net (code "56") (name "unconnected-(SX3-Pad9)") (class "Default")
      (node (ref "SX3") (pin "9") (pinfunction "9_9") (pintype "passive"))
    )
    (net (code "57") (name "unconnected-(SX4-Pad9)") (class "Default")
      (node (ref "SX4") (pin "9") (pinfunction "9_9") (pintype "passive"))
    )
  )
)
